# astronaut_mainboard.net
KiCad netlist of a schematic drawn in EAGLE
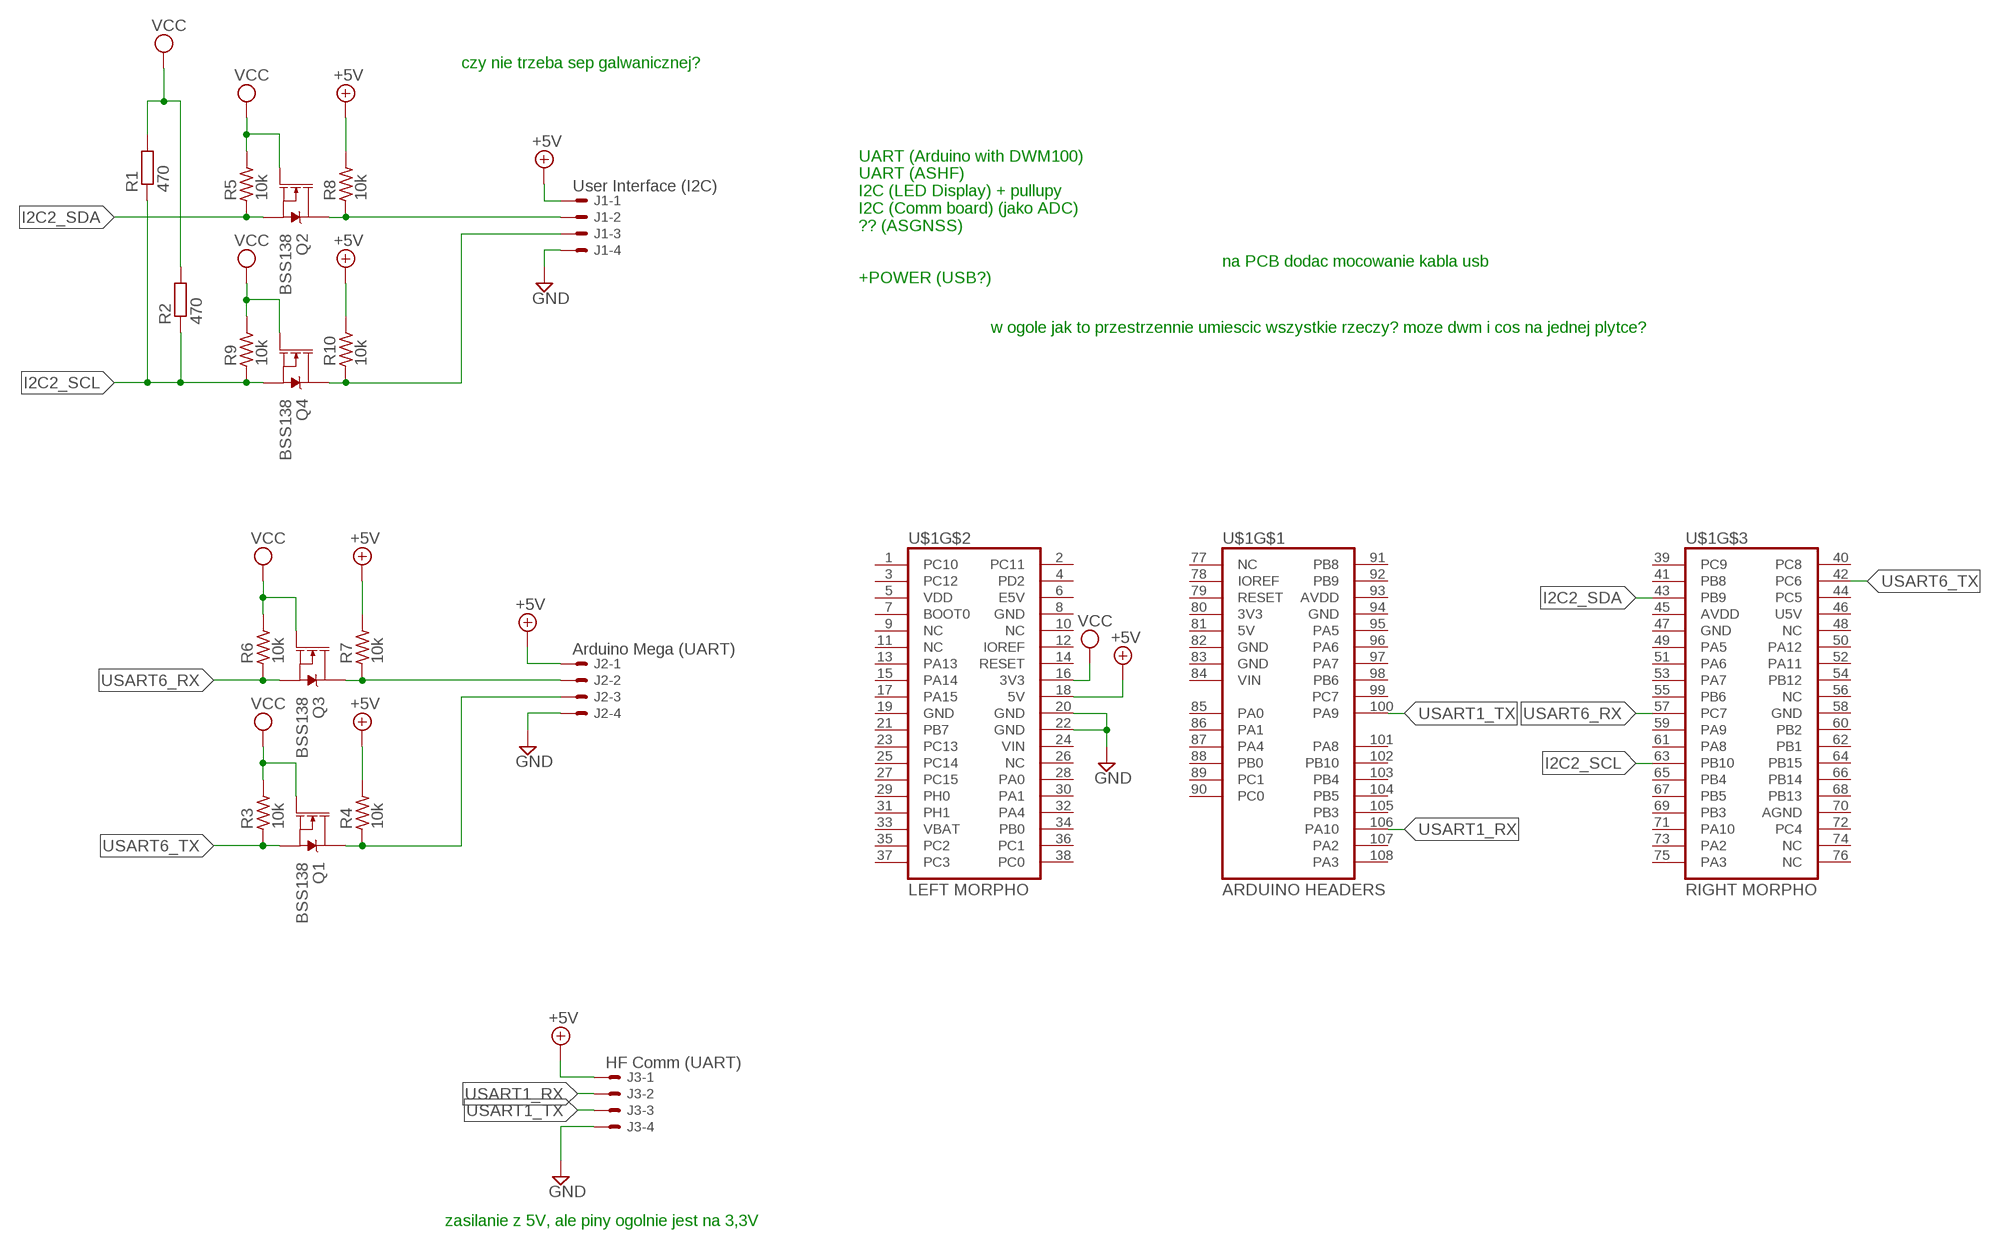
[diagram p0: schematic, sheet 1]

(export (version "E")
  (design (tool "Eeschema 10.0.6"))
  (components
    (comp (ref "J1")
      (value "User Interface (I2C)")
      (footprint "eagle-import:7395-04")
      (libsource (lib "eagle-import") (part "22-?-0405-7048"))
    )
    (comp (ref "J2")
      (value "Arduino Mega (UART)")
      (footprint "eagle-import:7395-04")
      (libsource (lib "eagle-import") (part "22-?-0405-7048"))
    )
    (comp (ref "J3")
      (value "HF Comm (UART)")
      (footprint "eagle-import:7395-04")
      (libsource (lib "eagle-import") (part "22-?-0405-7048"))
    )
    (comp (ref "Q1")
      (value "BSS138")
      (footprint "eagle-import:SOT23-3")
      (libsource (lib "eagle-import") (part "MOSFET-NCH-AO3404A"))
    )
    (comp (ref "Q2")
      (value "BSS138")
      (footprint "eagle-import:SOT23-3")
      (libsource (lib "eagle-import") (part "MOSFET-NCH-AO3404A"))
    )
    (comp (ref "Q3")
      (value "BSS138")
      (footprint "eagle-import:SOT23-3")
      (libsource (lib "eagle-import") (part "MOSFET-NCH-AO3404A"))
    )
    (comp (ref "Q4")
      (value "BSS138")
      (footprint "eagle-import:SOT23-3")
      (libsource (lib "eagle-import") (part "MOSFET-NCH-AO3404A"))
    )
    (comp (ref "R1")
      (value "470")
      (footprint "eagle-import:R0805")
      (libsource (lib "eagle-import") (part "R-EU_R0805"))
    )
    (comp (ref "R2")
      (value "470")
      (footprint "eagle-import:R0805")
      (libsource (lib "eagle-import") (part "R-EU_R0805"))
    )
    (comp (ref "R3")
      (value "10k")
      (footprint "eagle-import:R1206")
      (libsource (lib "eagle-import") (part "R_1206"))
    )
    (comp (ref "R4")
      (value "10k")
      (footprint "eagle-import:R1206")
      (libsource (lib "eagle-import") (part "R_1206"))
    )
    (comp (ref "R5")
      (value "10k")
      (footprint "eagle-import:R1206")
      (libsource (lib "eagle-import") (part "R_1206"))
    )
    (comp (ref "R6")
      (value "10k")
      (footprint "eagle-import:R1206")
      (libsource (lib "eagle-import") (part "R_1206"))
    )
    (comp (ref "R7")
      (value "10k")
      (footprint "eagle-import:R1206")
      (libsource (lib "eagle-import") (part "R_1206"))
    )
    (comp (ref "R8")
      (value "10k")
      (footprint "eagle-import:R1206")
      (libsource (lib "eagle-import") (part "R_1206"))
    )
    (comp (ref "R9")
      (value "10k")
      (footprint "eagle-import:R1206")
      (libsource (lib "eagle-import") (part "R_1206"))
    )
    (comp (ref "R10")
      (value "10k")
      (footprint "eagle-import:R1206")
      (libsource (lib "eagle-import") (part "R_1206"))
    )
    (comp (ref "U$1")
      (value "NUCLEO_F411RE")
      (footprint "eagle-import:ARDUINO+MORPHO")
      (libsource (lib "eagle-import") (part "NUCLEO_F411RE"))
    )
  )
  (nets
    (net (code "1") (name "+5V") (class "Default")
      (node (ref "J1") (pin "1") (pinfunction "S_1") (pintype "passive"))
      (node (ref "J2") (pin "1") (pinfunction "S_1") (pintype "passive"))
      (node (ref "J3") (pin "1") (pinfunction "S_1") (pintype "passive"))
      (node (ref "R10") (pin "2") (pinfunction "2_2") (pintype "passive"))
      (node (ref "R4") (pin "2") (pinfunction "2_2") (pintype "passive"))
      (node (ref "R7") (pin "2") (pinfunction "2_2") (pintype "passive"))
      (node (ref "R8") (pin "2") (pinfunction "2_2") (pintype "passive"))
      (node (ref "U$1") (pin "18") (pinfunction "5V_18") (pintype "bidirectional"))
    )
    (net (code "2") (name "GND") (class "Default")
      (node (ref "J1") (pin "4") (pinfunction "S_4") (pintype "passive"))
      (node (ref "J2") (pin "4") (pinfunction "S_4") (pintype "passive"))
      (node (ref "J3") (pin "4") (pinfunction "S_4") (pintype "passive"))
      (node (ref "U$1") (pin "20") (pinfunction "GND_20") (pintype "bidirectional"))
      (node (ref "U$1") (pin "22") (pinfunction "GND_22") (pintype "bidirectional"))
    )
    (net (code "3") (name "I2C2_SCL") (class "Default")
      (node (ref "Q4") (pin "2") (pinfunction "S_2") (pintype "bidirectional"))
      (node (ref "R1") (pin "1") (pinfunction "1_1") (pintype "passive"))
      (node (ref "R2") (pin "1") (pinfunction "1_1") (pintype "passive"))
      (node (ref "R9") (pin "1") (pinfunction "1_1") (pintype "passive"))
      (node (ref "U$1") (pin "63") (pinfunction "PB10_63") (pintype "input"))
    )
    (net (code "4") (name "I2C2_SDA") (class "Default")
      (node (ref "Q2") (pin "2") (pinfunction "S_2") (pintype "bidirectional"))
      (node (ref "R5") (pin "1") (pinfunction "1_1") (pintype "passive"))
      (node (ref "U$1") (pin "43") (pinfunction "PB9_43") (pintype "input"))
    )
    (net (code "5") (name "Net-(J1B-S)") (class "Default")
      (node (ref "J1") (pin "2") (pinfunction "S_2") (pintype "passive"))
      (node (ref "Q2") (pin "3") (pinfunction "D_3") (pintype "bidirectional"))
      (node (ref "R8") (pin "1") (pinfunction "1_1") (pintype "passive"))
    )
    (net (code "6") (name "Net-(J1C-S)") (class "Default")
      (node (ref "J1") (pin "3") (pinfunction "S_3") (pintype "passive"))
      (node (ref "Q4") (pin "3") (pinfunction "D_3") (pintype "bidirectional"))
      (node (ref "R10") (pin "1") (pinfunction "1_1") (pintype "passive"))
    )
    (net (code "7") (name "Net-(J2B-S)") (class "Default")
      (node (ref "J2") (pin "2") (pinfunction "S_2") (pintype "passive"))
      (node (ref "Q3") (pin "3") (pinfunction "D_3") (pintype "bidirectional"))
      (node (ref "R7") (pin "1") (pinfunction "1_1") (pintype "passive"))
    )
    (net (code "8") (name "Net-(J2C-S)") (class "Default")
      (node (ref "J2") (pin "3") (pinfunction "S_3") (pintype "passive"))
      (node (ref "Q1") (pin "3") (pinfunction "D_3") (pintype "bidirectional"))
      (node (ref "R4") (pin "1") (pinfunction "1_1") (pintype "passive"))
    )
    (net (code "9") (name "USART1_RX") (class "Default")
      (node (ref "J3") (pin "2") (pinfunction "S_2") (pintype "passive"))
      (node (ref "U$1") (pin "106") (pinfunction "PA10_106") (pintype "bidirectional"))
    )
    (net (code "10") (name "USART1_TX") (class "Default")
      (node (ref "J3") (pin "3") (pinfunction "S_3") (pintype "passive"))
      (node (ref "U$1") (pin "100") (pinfunction "PA9_100") (pintype "bidirectional"))
    )
    (net (code "11") (name "USART6_RX") (class "Default")
      (node (ref "Q3") (pin "2") (pinfunction "S_2") (pintype "bidirectional"))
      (node (ref "R6") (pin "1") (pinfunction "1_1") (pintype "passive"))
      (node (ref "U$1") (pin "57") (pinfunction "PC7_57") (pintype "input"))
    )
    (net (code "12") (name "USART6_TX") (class "Default")
      (node (ref "Q1") (pin "2") (pinfunction "S_2") (pintype "bidirectional"))
      (node (ref "R3") (pin "1") (pinfunction "1_1") (pintype "passive"))
      (node (ref "U$1") (pin "42") (pinfunction "PC6_42") (pintype "output"))
    )
    (net (code "13") (name "VCC") (class "Default")
      (node (ref "Q1") (pin "1") (pinfunction "G_1") (pintype "bidirectional"))
      (node (ref "Q2") (pin "1") (pinfunction "G_1") (pintype "bidirectional"))
      (node (ref "Q3") (pin "1") (pinfunction "G_1") (pintype "bidirectional"))
      (node (ref "Q4") (pin "1") (pinfunction "G_1") (pintype "bidirectional"))
      (node (ref "R1") (pin "2") (pinfunction "2_2") (pintype "passive"))
      (node (ref "R2") (pin "2") (pinfunction "2_2") (pintype "passive"))
      (node (ref "R3") (pin "2") (pinfunction "2_2") (pintype "passive"))
      (node (ref "R5") (pin "2") (pinfunction "2_2") (pintype "passive"))
      (node (ref "R6") (pin "2") (pinfunction "2_2") (pintype "passive"))
      (node (ref "R9") (pin "2") (pinfunction "2_2") (pintype "passive"))
      (node (ref "U$1") (pin "16") (pinfunction "3V3_16") (pintype "output"))
    )
    (net (code "14") (name "unconnected-(U$1A-3V3-Pad80)") (class "Default")
      (node (ref "U$1") (pin "80") (pinfunction "3V3_80") (pintype "input"))
    )
    (net (code "15") (name "unconnected-(U$1A-5V-Pad81)") (class "Default")
      (node (ref "U$1") (pin "81") (pinfunction "5V_81") (pintype "bidirectional"))
    )
    (net (code "16") (name "unconnected-(U$1A-AVDD-Pad93)") (class "Default")
      (node (ref "U$1") (pin "93") (pinfunction "AVDD_93") (pintype "output"))
    )
    (net (code "17") (name "unconnected-(U$1A-GND-Pad82)") (class "Default")
      (node (ref "U$1") (pin "82") (pinfunction "GND_82") (pintype "input"))
    )
    (net (code "18") (name "unconnected-(U$1A-GND-Pad83)") (class "Default")
      (node (ref "U$1") (pin "83") (pinfunction "GND_83") (pintype "input"))
    )
    (net (code "19") (name "unconnected-(U$1A-GND-Pad94)") (class "Default")
      (node (ref "U$1") (pin "94") (pinfunction "GND_94") (pintype "output"))
    )
    (net (code "20") (name "unconnected-(U$1A-IOREF-Pad78)") (class "Default")
      (node (ref "U$1") (pin "78") (pinfunction "IOREF_78") (pintype "input"))
    )
    (net (code "21") (name "unconnected-(U$1A-NC-Pad77)") (class "Default")
      (node (ref "U$1") (pin "77") (pinfunction "NC_77") (pintype "input"))
    )
    (net (code "22") (name "unconnected-(U$1A-PA0-Pad85)") (class "Default")
      (node (ref "U$1") (pin "85") (pinfunction "PA0_85") (pintype "input"))
    )
    (net (code "23") (name "unconnected-(U$1A-PA1-Pad86)") (class "Default")
      (node (ref "U$1") (pin "86") (pinfunction "PA1_86") (pintype "input"))
    )
    (net (code "24") (name "unconnected-(U$1A-PA2-Pad107)") (class "Default")
      (node (ref "U$1") (pin "107") (pinfunction "PA2_107") (pintype "bidirectional"))
    )
    (net (code "25") (name "unconnected-(U$1A-PA3-Pad108)") (class "Default")
      (node (ref "U$1") (pin "108") (pinfunction "PA3_108") (pintype "bidirectional"))
    )
    (net (code "26") (name "unconnected-(U$1A-PA4-Pad87)") (class "Default")
      (node (ref "U$1") (pin "87") (pinfunction "PA4_87") (pintype "input"))
    )
    (net (code "27") (name "unconnected-(U$1A-PA5-Pad95)") (class "Default")
      (node (ref "U$1") (pin "95") (pinfunction "PA5_95") (pintype "output"))
    )
    (net (code "28") (name "unconnected-(U$1A-PA6-Pad96)") (class "Default")
      (node (ref "U$1") (pin "96") (pinfunction "PA6_96") (pintype "output"))
    )
    (net (code "29") (name "unconnected-(U$1A-PA7-Pad97)") (class "Default")
      (node (ref "U$1") (pin "97") (pinfunction "PA7_97") (pintype "output"))
    )
    (net (code "30") (name "unconnected-(U$1A-PA8-Pad101)") (class "Default")
      (node (ref "U$1") (pin "101") (pinfunction "PA8_101") (pintype "bidirectional"))
    )
    (net (code "31") (name "unconnected-(U$1A-PB0-Pad88)") (class "Default")
      (node (ref "U$1") (pin "88") (pinfunction "PB0_88") (pintype "input"))
    )
    (net (code "32") (name "unconnected-(U$1A-PB3-Pad105)") (class "Default")
      (node (ref "U$1") (pin "105") (pinfunction "PB3_105") (pintype "bidirectional"))
    )
    (net (code "33") (name "unconnected-(U$1A-PB4-Pad103)") (class "Default")
      (node (ref "U$1") (pin "103") (pinfunction "PB4_103") (pintype "bidirectional"))
    )
    (net (code "34") (name "unconnected-(U$1A-PB5-Pad104)") (class "Default")
      (node (ref "U$1") (pin "104") (pinfunction "PB5_104") (pintype "bidirectional"))
    )
    (net (code "35") (name "unconnected-(U$1A-PB6-Pad98)") (class "Default")
      (node (ref "U$1") (pin "98") (pinfunction "PB6_98") (pintype "output"))
    )
    (net (code "36") (name "unconnected-(U$1A-PB8-Pad91)") (class "Default")
      (node (ref "U$1") (pin "91") (pinfunction "PB8_91") (pintype "output"))
    )
    (net (code "37") (name "unconnected-(U$1A-PB9-Pad92)") (class "Default")
      (node (ref "U$1") (pin "92") (pinfunction "PB9_92") (pintype "output"))
    )
    (net (code "38") (name "unconnected-(U$1A-PB10-Pad102)") (class "Default")
      (node (ref "U$1") (pin "102") (pinfunction "PB10_102") (pintype "bidirectional"))
    )
    (net (code "39") (name "unconnected-(U$1A-PC0-Pad90)") (class "Default")
      (node (ref "U$1") (pin "90") (pinfunction "PC0_90") (pintype "input"))
    )
    (net (code "40") (name "unconnected-(U$1A-PC1-Pad89)") (class "Default")
      (node (ref "U$1") (pin "89") (pinfunction "PC1_89") (pintype "input"))
    )
    (net (code "41") (name "unconnected-(U$1A-PC7-Pad99)") (class "Default")
      (node (ref "U$1") (pin "99") (pinfunction "PC7_99") (pintype "bidirectional"))
    )
    (net (code "42") (name "unconnected-(U$1A-RESET-Pad79)") (class "Default")
      (node (ref "U$1") (pin "79") (pinfunction "RESET_79") (pintype "input"))
    )
    (net (code "43") (name "unconnected-(U$1A-VIN-Pad84)") (class "Default")
      (node (ref "U$1") (pin "84") (pinfunction "VIN_84") (pintype "input"))
    )
    (net (code "44") (name "unconnected-(U$1B-BOOT0-Pad7)") (class "Default")
      (node (ref "U$1") (pin "7") (pinfunction "BOOT0_7") (pintype "input"))
    )
    (net (code "45") (name "unconnected-(U$1B-E5V-Pad6)") (class "Default")
      (node (ref "U$1") (pin "6") (pinfunction "E5V_6") (pintype "output"))
    )
    (net (code "46") (name "unconnected-(U$1B-GND-Pad8)") (class "Default")
      (node (ref "U$1") (pin "8") (pinfunction "GND_8") (pintype "output"))
    )
    (net (code "47") (name "unconnected-(U$1B-GND-Pad19)") (class "Default")
      (node (ref "U$1") (pin "19") (pinfunction "GND_19") (pintype "input"))
    )
    (net (code "48") (name "unconnected-(U$1B-IOREF-Pad12)") (class "Default")
      (node (ref "U$1") (pin "12") (pinfunction "IOREF_12") (pintype "output"))
    )
    (net (code "49") (name "unconnected-(U$1B-NC-Pad9)") (class "Default")
      (node (ref "U$1") (pin "9") (pinfunction "NC_9") (pintype "input"))
    )
    (net (code "50") (name "unconnected-(U$1B-NC-Pad10)") (class "Default")
      (node (ref "U$1") (pin "10") (pinfunction "NC_10") (pintype "output"))
    )
    (net (code "51") (name "unconnected-(U$1B-NC-Pad11)") (class "Default")
      (node (ref "U$1") (pin "11") (pinfunction "NC_11") (pintype "input"))
    )
    (net (code "52") (name "unconnected-(U$1B-NC-Pad26)") (class "Default")
      (node (ref "U$1") (pin "26") (pinfunction "NC_26") (pintype "bidirectional"))
    )
    (net (code "53") (name "unconnected-(U$1B-PA0-Pad28)") (class "Default")
      (node (ref "U$1") (pin "28") (pinfunction "PA0_28") (pintype "bidirectional"))
    )
    (net (code "54") (name "unconnected-(U$1B-PA1-Pad30)") (class "Default")
      (node (ref "U$1") (pin "30") (pinfunction "PA1_30") (pintype "bidirectional"))
    )
    (net (code "55") (name "unconnected-(U$1B-PA4-Pad32)") (class "Default")
      (node (ref "U$1") (pin "32") (pinfunction "PA4_32") (pintype "bidirectional"))
    )
    (net (code "56") (name "unconnected-(U$1B-PA13-Pad13)") (class "Default")
      (node (ref "U$1") (pin "13") (pinfunction "PA13_13") (pintype "input"))
    )
    (net (code "57") (name "unconnected-(U$1B-PA14-Pad15)") (class "Default")
      (node (ref "U$1") (pin "15") (pinfunction "PA14_15") (pintype "input"))
    )
    (net (code "58") (name "unconnected-(U$1B-PA15-Pad17)") (class "Default")
      (node (ref "U$1") (pin "17") (pinfunction "PA15_17") (pintype "input"))
    )
    (net (code "59") (name "unconnected-(U$1B-PB0-Pad34)") (class "Default")
      (node (ref "U$1") (pin "34") (pinfunction "PB0_34") (pintype "bidirectional"))
    )
    (net (code "60") (name "unconnected-(U$1B-PB7-Pad21)") (class "Default")
      (node (ref "U$1") (pin "21") (pinfunction "PB7_21") (pintype "input"))
    )
    (net (code "61") (name "unconnected-(U$1B-PC0-Pad38)") (class "Default")
      (node (ref "U$1") (pin "38") (pinfunction "PC0_38") (pintype "bidirectional"))
    )
    (net (code "62") (name "unconnected-(U$1B-PC1-Pad36)") (class "Default")
      (node (ref "U$1") (pin "36") (pinfunction "PC1_36") (pintype "bidirectional"))
    )
    (net (code "63") (name "unconnected-(U$1B-PC2-Pad35)") (class "Default")
      (node (ref "U$1") (pin "35") (pinfunction "PC2_35") (pintype "bidirectional"))
    )
    (net (code "64") (name "unconnected-(U$1B-PC3-Pad37)") (class "Default")
      (node (ref "U$1") (pin "37") (pinfunction "PC3_37") (pintype "bidirectional"))
    )
    (net (code "65") (name "unconnected-(U$1B-PC10-Pad1)") (class "Default")
      (node (ref "U$1") (pin "1") (pinfunction "PC10_1") (pintype "input"))
    )
    (net (code "66") (name "unconnected-(U$1B-PC11-Pad2)") (class "Default")
      (node (ref "U$1") (pin "2") (pinfunction "PC11_2") (pintype "output"))
    )
    (net (code "67") (name "unconnected-(U$1B-PC12-Pad3)") (class "Default")
      (node (ref "U$1") (pin "3") (pinfunction "PC12_3") (pintype "input"))
    )
    (net (code "68") (name "unconnected-(U$1B-PC13-Pad23)") (class "Default")
      (node (ref "U$1") (pin "23") (pinfunction "PC13_23") (pintype "input"))
    )
    (net (code "69") (name "unconnected-(U$1B-PC14-Pad25)") (class "Default")
      (node (ref "U$1") (pin "25") (pinfunction "PC14_25") (pintype "input"))
    )
    (net (code "70") (name "unconnected-(U$1B-PC15-Pad27)") (class "Default")
      (node (ref "U$1") (pin "27") (pinfunction "PC15_27") (pintype "input"))
    )
    (net (code "71") (name "unconnected-(U$1B-PD2-Pad4)") (class "Default")
      (node (ref "U$1") (pin "4") (pinfunction "PD2_4") (pintype "output"))
    )
    (net (code "72") (name "unconnected-(U$1B-PH0-Pad29)") (class "Default")
      (node (ref "U$1") (pin "29") (pinfunction "PH0_29") (pintype "bidirectional"))
    )
    (net (code "73") (name "unconnected-(U$1B-PH1-Pad31)") (class "Default")
      (node (ref "U$1") (pin "31") (pinfunction "PH1_31") (pintype "bidirectional"))
    )
    (net (code "74") (name "unconnected-(U$1B-RESET-Pad14)") (class "Default")
      (node (ref "U$1") (pin "14") (pinfunction "RESET_14") (pintype "output"))
    )
    (net (code "75") (name "unconnected-(U$1B-VBAT-Pad33)") (class "Default")
      (node (ref "U$1") (pin "33") (pinfunction "VBAT_33") (pintype "bidirectional"))
    )
    (net (code "76") (name "unconnected-(U$1B-VDD-Pad5)") (class "Default")
      (node (ref "U$1") (pin "5") (pinfunction "VDD_5") (pintype "input"))
    )
    (net (code "77") (name "unconnected-(U$1B-VIN-Pad24)") (class "Default")
      (node (ref "U$1") (pin "24") (pinfunction "VIN_24") (pintype "bidirectional"))
    )
    (net (code "78") (name "unconnected-(U$1C-AGND-Pad70)") (class "Default")
      (node (ref "U$1") (pin "70") (pinfunction "AGND_70") (pintype "bidirectional"))
    )
    (net (code "79") (name "unconnected-(U$1C-AVDD-Pad45)") (class "Default")
      (node (ref "U$1") (pin "45") (pinfunction "AVDD_45") (pintype "input"))
    )
    (net (code "80") (name "unconnected-(U$1C-GND-Pad47)") (class "Default")
      (node (ref "U$1") (pin "47") (pinfunction "GND_47") (pintype "input"))
    )
    (net (code "81") (name "unconnected-(U$1C-GND-Pad58)") (class "Default")
      (node (ref "U$1") (pin "58") (pinfunction "GND_58") (pintype "bidirectional"))
    )
    (net (code "82") (name "unconnected-(U$1C-NC-Pad48)") (class "Default")
      (node (ref "U$1") (pin "48") (pinfunction "NC_48") (pintype "output"))
    )
    (net (code "83") (name "unconnected-(U$1C-NC-Pad56)") (class "Default")
      (node (ref "U$1") (pin "56") (pinfunction "NC_56") (pintype "bidirectional"))
    )
    (net (code "84") (name "unconnected-(U$1C-NC-Pad74)") (class "Default")
      (node (ref "U$1") (pin "74") (pinfunction "NC_74") (pintype "bidirectional"))
    )
    (net (code "85") (name "unconnected-(U$1C-NC-Pad76)") (class "Default")
      (node (ref "U$1") (pin "76") (pinfunction "NC_76") (pintype "bidirectional"))
    )
    (net (code "86") (name "unconnected-(U$1C-PA2-Pad73)") (class "Default")
      (node (ref "U$1") (pin "73") (pinfunction "PA2_73") (pintype "bidirectional"))
    )
    (net (code "87") (name "unconnected-(U$1C-PA3-Pad75)") (class "Default")
      (node (ref "U$1") (pin "75") (pinfunction "PA3_75") (pintype "bidirectional"))
    )
    (net (code "88") (name "unconnected-(U$1C-PA5-Pad49)") (class "Default")
      (node (ref "U$1") (pin "49") (pinfunction "PA5_49") (pintype "input"))
    )
    (net (code "89") (name "unconnected-(U$1C-PA6-Pad51)") (class "Default")
      (node (ref "U$1") (pin "51") (pinfunction "PA6_51") (pintype "input"))
    )
    (net (code "90") (name "unconnected-(U$1C-PA7-Pad53)") (class "Default")
      (node (ref "U$1") (pin "53") (pinfunction "PA7_53") (pintype "input"))
    )
    (net (code "91") (name "unconnected-(U$1C-PA8-Pad61)") (class "Default")
      (node (ref "U$1") (pin "61") (pinfunction "PA8_61") (pintype "input"))
    )
    (net (code "92") (name "unconnected-(U$1C-PA9-Pad59)") (class "Default")
      (node (ref "U$1") (pin "59") (pinfunction "PA9_59") (pintype "input"))
    )
    (net (code "93") (name "unconnected-(U$1C-PA10-Pad71)") (class "Default")
      (node (ref "U$1") (pin "71") (pinfunction "PA10_71") (pintype "bidirectional"))
    )
    (net (code "94") (name "unconnected-(U$1C-PA11-Pad52)") (class "Default")
      (node (ref "U$1") (pin "52") (pinfunction "PA11_52") (pintype "output"))
    )
    (net (code "95") (name "unconnected-(U$1C-PA12-Pad50)") (class "Default")
      (node (ref "U$1") (pin "50") (pinfunction "PA12_50") (pintype "output"))
    )
    (net (code "96") (name "unconnected-(U$1C-PB1-Pad62)") (class "Default")
      (node (ref "U$1") (pin "62") (pinfunction "PB1_62") (pintype "bidirectional"))
    )
    (net (code "97") (name "unconnected-(U$1C-PB2-Pad60)") (class "Default")
      (node (ref "U$1") (pin "60") (pinfunction "PB2_60") (pintype "bidirectional"))
    )
    (net (code "98") (name "unconnected-(U$1C-PB3-Pad69)") (class "Default")
      (node (ref "U$1") (pin "69") (pinfunction "PB3_69") (pintype "bidirectional"))
    )
    (net (code "99") (name "unconnected-(U$1C-PB4-Pad65)") (class "Default")
      (node (ref "U$1") (pin "65") (pinfunction "PB4_65") (pintype "input"))
    )
    (net (code "100") (name "unconnected-(U$1C-PB5-Pad67)") (class "Default")
      (node (ref "U$1") (pin "67") (pinfunction "PB5_67") (pintype "bidirectional"))
    )
    (net (code "101") (name "unconnected-(U$1C-PB6-Pad55)") (class "Default")
      (node (ref "U$1") (pin "55") (pinfunction "PB6_55") (pintype "input"))
    )
    (net (code "102") (name "unconnected-(U$1C-PB8-Pad41)") (class "Default")
      (node (ref "U$1") (pin "41") (pinfunction "PB8_41") (pintype "input"))
    )
    (net (code "103") (name "unconnected-(U$1C-PB12-Pad54)") (class "Default")
      (node (ref "U$1") (pin "54") (pinfunction "PB12_54") (pintype "output"))
    )
    (net (code "104") (name "unconnected-(U$1C-PB13-Pad68)") (class "Default")
      (node (ref "U$1") (pin "68") (pinfunction "PB13_68") (pintype "bidirectional"))
    )
    (net (code "105") (name "unconnected-(U$1C-PB14-Pad66)") (class "Default")
      (node (ref "U$1") (pin "66") (pinfunction "PB14_66") (pintype "bidirectional"))
    )
    (net (code "106") (name "unconnected-(U$1C-PB15-Pad64)") (class "Default")
      (node (ref "U$1") (pin "64") (pinfunction "PB15_64") (pintype "bidirectional"))
    )
    (net (code "107") (name "unconnected-(U$1C-PC4-Pad72)") (class "Default")
      (node (ref "U$1") (pin "72") (pinfunction "PC4_72") (pintype "bidirectional"))
    )
    (net (code "108") (name "unconnected-(U$1C-PC5-Pad44)") (class "Default")
      (node (ref "U$1") (pin "44") (pinfunction "PC5_44") (pintype "output"))
    )
    (net (code "109") (name "unconnected-(U$1C-PC8-Pad40)") (class "Default")
      (node (ref "U$1") (pin "40") (pinfunction "PC8_40") (pintype "output"))
    )
    (net (code "110") (name "unconnected-(U$1C-PC9-Pad39)") (class "Default")
      (node (ref "U$1") (pin "39") (pinfunction "PC9_39") (pintype "input"))
    )
    (net (code "111") (name "unconnected-(U$1C-U5V-Pad46)") (class "Default")
      (node (ref "U$1") (pin "46") (pinfunction "U5V_46") (pintype "output"))
    )
  )
)
